# HW2.net
KiCad netlist of a schematic drawn in EAGLE
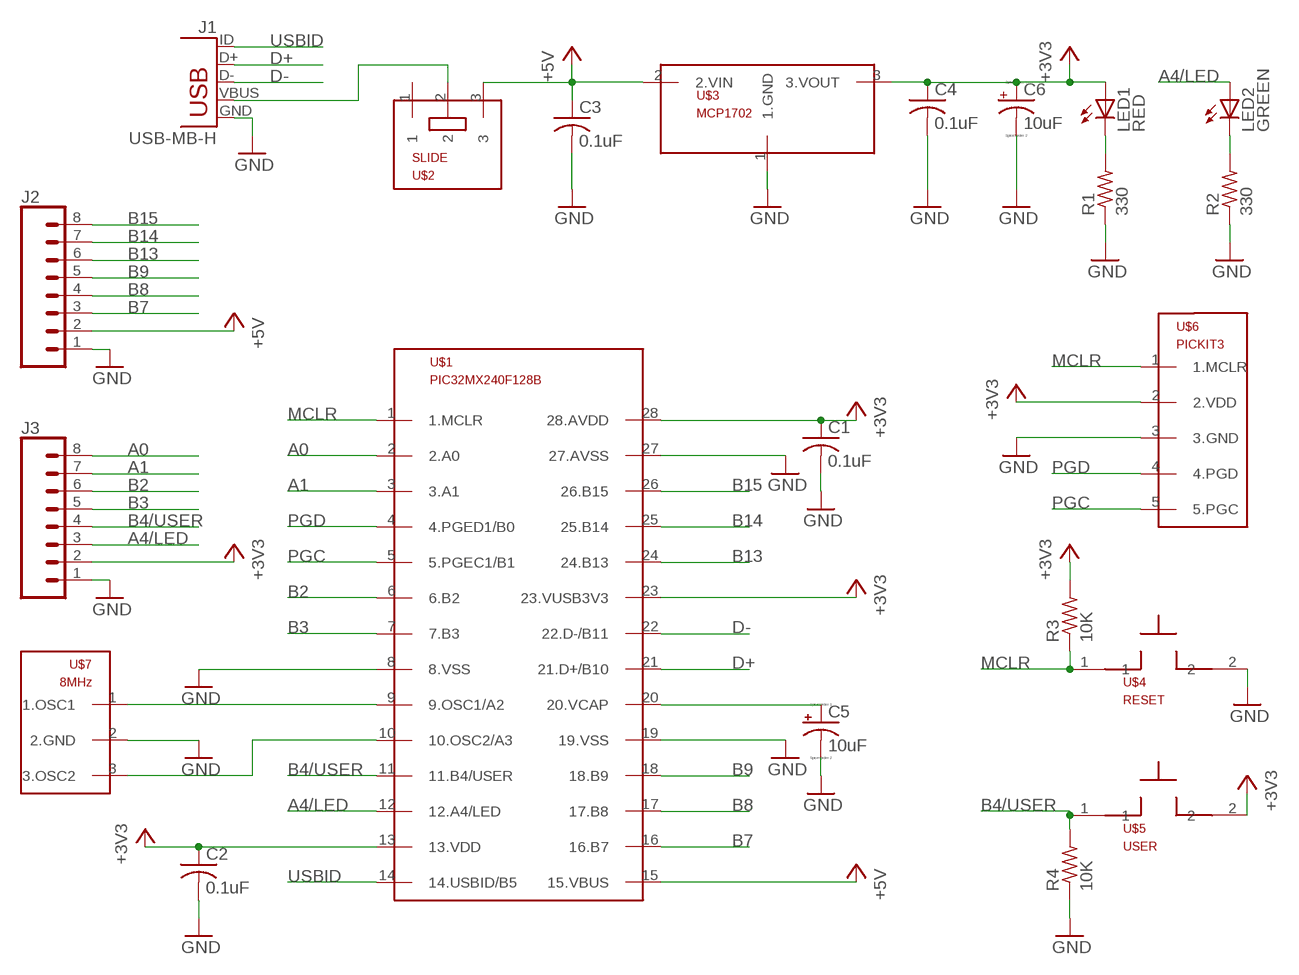
[diagram p0: schematic, sheet 1]

(export (version "E")
  (design (tool "Eeschema 10.0.6"))
  (components
    (comp (ref "C1")
      (value "0.1uF")
      (footprint "eagle-import:C025-025X050")
      (libsource (lib "eagle-import") (part "C-US025-025X050"))
    )
    (comp (ref "C2")
      (value "0.1uF")
      (footprint "eagle-import:C025-025X050")
      (libsource (lib "eagle-import") (part "C-US025-025X050"))
    )
    (comp (ref "C3")
      (value "0.1uF")
      (footprint "eagle-import:C025-025X050")
      (libsource (lib "eagle-import") (part "C-US025-025X050"))
    )
    (comp (ref "C4")
      (value "0.1uF")
      (footprint "eagle-import:C025-025X050")
      (libsource (lib "eagle-import") (part "C-US025-025X050"))
    )
    (comp (ref "C5")
      (value "10uF")
      (footprint "eagle-import:B45181B")
      (libsource (lib "eagle-import") (part "CPOL-USB45181B"))
    )
    (comp (ref "C6")
      (value "10uF")
      (footprint "eagle-import:B45181B")
      (libsource (lib "eagle-import") (part "CPOL-USB45181B"))
    )
    (comp (ref "J1")
      (value "USB-MB-H")
      (footprint "eagle-import:USB-MB-H")
      (libsource (lib "eagle-import") (part "USB-MB-H"))
    )
    (comp (ref "J2")
      (value "CONN_08\"")
      (footprint "eagle-import:1X08")
      (libsource (lib "eagle-import") (part "CONN_08{dblquote}"))
    )
    (comp (ref "J3")
      (value "CONN_08\"")
      (footprint "eagle-import:1X08")
      (libsource (lib "eagle-import") (part "CONN_08{dblquote}"))
    )
    (comp (ref "LED1")
      (value "RED")
      (footprint "eagle-import:LED3MM")
      (libsource (lib "eagle-import") (part "LED3MM"))
    )
    (comp (ref "LED2")
      (value "GREEN")
      (footprint "eagle-import:LED3MM")
      (libsource (lib "eagle-import") (part "LED3MM"))
    )
    (comp (ref "R1")
      (value "330")
      (footprint "eagle-import:0207_10")
      (libsource (lib "eagle-import") (part "R-US_0207/10"))
    )
    (comp (ref "R2")
      (value "330")
      (footprint "eagle-import:0207_10")
      (libsource (lib "eagle-import") (part "R-US_0207/10"))
    )
    (comp (ref "R3")
      (value "10K")
      (footprint "eagle-import:0207_10")
      (libsource (lib "eagle-import") (part "R-US_0207/10"))
    )
    (comp (ref "R4")
      (value "10K")
      (footprint "eagle-import:0207_10")
      (libsource (lib "eagle-import") (part "R-US_0207/10"))
    )
    (comp (ref "U$1")
      (value "PIC32MX240F128B")
      (footprint "eagle-import:DIL28-3")
      (libsource (lib "eagle-import") (part "PIC32MX240F128B"))
    )
    (comp (ref "U$2")
      (value "SLIDE")
      (footprint "eagle-import:SLIDE")
      (libsource (lib "eagle-import") (part "SLIDE"))
    )
    (comp (ref "U$3")
      (value "MCP1702")
      (footprint "eagle-import:TO92")
      (libsource (lib "eagle-import") (part "MCP1702"))
    )
    (comp (ref "U$4")
      (value "RESET")
      (footprint "eagle-import:PUSHBUTTON")
      (libsource (lib "eagle-import") (part "PUSHBUTTON"))
    )
    (comp (ref "U$5")
      (value "USER")
      (footprint "eagle-import:PUSHBUTTON")
      (libsource (lib "eagle-import") (part "PUSHBUTTON"))
    )
    (comp (ref "U$6")
      (value "PICKIT3")
      (footprint "eagle-import:1X05")
      (libsource (lib "eagle-import") (part "PICKIT3"))
    )
    (comp (ref "U$7")
      (value "8MHz")
      (footprint "eagle-import:OSC")
      (libsource (lib "eagle-import") (part "OSC"))
    )
  )
  (nets
    (net (code "1") (name "+3V3") (class "Default")
      (node (ref "C1") (pin "1") (pinfunction "1_1") (pintype "passive"))
      (node (ref "C2") (pin "1") (pinfunction "1_1") (pintype "passive"))
      (node (ref "C4") (pin "1") (pinfunction "1_1") (pintype "passive"))
      (node (ref "C6") (pin "+") (pinfunction "+_+") (pintype "passive"))
      (node (ref "J3") (pin "2") (pinfunction "2_2") (pintype "passive"))
      (node (ref "LED1") (pin "A") (pinfunction "A_A") (pintype "passive"))
      (node (ref "R3") (pin "2") (pinfunction "2_2") (pintype "passive"))
      (node (ref "U$1") (pin "13") (pinfunction "13.VDD_13") (pintype "bidirectional"))
      (node (ref "U$1") (pin "23") (pinfunction "23.VUSB3V3_23") (pintype "bidirectional"))
      (node (ref "U$1") (pin "28") (pinfunction "28.AVDD_28") (pintype "bidirectional"))
      (node (ref "U$3") (pin "3") (pinfunction "3.VOUT_3") (pintype "bidirectional"))
      (node (ref "U$5") (pin "2") (pinfunction "2_2") (pintype "bidirectional"))
      (node (ref "U$6") (pin "2") (pinfunction "2.VDD_2") (pintype "bidirectional"))
    )
    (net (code "2") (name "+5V") (class "Default")
      (node (ref "C3") (pin "1") (pinfunction "1_1") (pintype "passive"))
      (node (ref "J2") (pin "2") (pinfunction "2_2") (pintype "passive"))
      (node (ref "U$1") (pin "15") (pinfunction "15.VBUS_15") (pintype "bidirectional"))
      (node (ref "U$2") (pin "3") (pinfunction "3_3") (pintype "bidirectional"))
      (node (ref "U$3") (pin "2") (pinfunction "2.VIN_2") (pintype "bidirectional"))
    )
    (net (code "3") (name "/A0") (class "Default")
      (node (ref "J3") (pin "8") (pinfunction "8_8") (pintype "passive"))
      (node (ref "U$1") (pin "2") (pinfunction "2.A0_2") (pintype "bidirectional"))
    )
    (net (code "4") (name "/A1") (class "Default")
      (node (ref "J3") (pin "7") (pinfunction "7_7") (pintype "passive"))
      (node (ref "U$1") (pin "3") (pinfunction "3.A1_3") (pintype "bidirectional"))
    )
    (net (code "5") (name "/A4{slash}LED") (class "Default")
      (node (ref "J3") (pin "3") (pinfunction "3_3") (pintype "passive"))
      (node (ref "LED2") (pin "A") (pinfunction "A_A") (pintype "passive"))
      (node (ref "U$1") (pin "12") (pinfunction "12.A4/LED_12") (pintype "bidirectional"))
    )
    (net (code "6") (name "/B2") (class "Default")
      (node (ref "J3") (pin "6") (pinfunction "6_6") (pintype "passive"))
      (node (ref "U$1") (pin "6") (pinfunction "6.B2_6") (pintype "bidirectional"))
    )
    (net (code "7") (name "/B3") (class "Default")
      (node (ref "J3") (pin "5") (pinfunction "5_5") (pintype "passive"))
      (node (ref "U$1") (pin "7") (pinfunction "7.B3_7") (pintype "bidirectional"))
    )
    (net (code "8") (name "/B4{slash}USER") (class "Default")
      (node (ref "J3") (pin "4") (pinfunction "4_4") (pintype "passive"))
      (node (ref "R4") (pin "2") (pinfunction "2_2") (pintype "passive"))
      (node (ref "U$1") (pin "11") (pinfunction "11.B4/USER_11") (pintype "bidirectional"))
      (node (ref "U$5") (pin "1") (pinfunction "1_1") (pintype "bidirectional"))
    )
    (net (code "9") (name "/B7") (class "Default")
      (node (ref "J2") (pin "3") (pinfunction "3_3") (pintype "passive"))
      (node (ref "U$1") (pin "16") (pinfunction "16.B7_16") (pintype "bidirectional"))
    )
    (net (code "10") (name "/B8") (class "Default")
      (node (ref "J2") (pin "4") (pinfunction "4_4") (pintype "passive"))
      (node (ref "U$1") (pin "17") (pinfunction "17.B8_17") (pintype "bidirectional"))
    )
    (net (code "11") (name "/B9") (class "Default")
      (node (ref "J2") (pin "5") (pinfunction "5_5") (pintype "passive"))
      (node (ref "U$1") (pin "18") (pinfunction "18.B9_18") (pintype "bidirectional"))
    )
    (net (code "12") (name "/B13") (class "Default")
      (node (ref "J2") (pin "6") (pinfunction "6_6") (pintype "passive"))
      (node (ref "U$1") (pin "24") (pinfunction "24.B13_24") (pintype "bidirectional"))
    )
    (net (code "13") (name "/B14") (class "Default")
      (node (ref "J2") (pin "7") (pinfunction "7_7") (pintype "passive"))
      (node (ref "U$1") (pin "25") (pinfunction "25.B14_25") (pintype "bidirectional"))
    )
    (net (code "14") (name "/B15") (class "Default")
      (node (ref "J2") (pin "8") (pinfunction "8_8") (pintype "passive"))
      (node (ref "U$1") (pin "26") (pinfunction "26.B15_26") (pintype "bidirectional"))
    )
    (net (code "15") (name "/D+") (class "Default")
      (node (ref "J1") (pin "D+") (pinfunction "D+_D+") (pintype "bidirectional"))
      (node (ref "U$1") (pin "21") (pinfunction "21.D+/B10_21") (pintype "bidirectional"))
    )
    (net (code "16") (name "/D-") (class "Default")
      (node (ref "J1") (pin "D-") (pinfunction "D-_D-") (pintype "bidirectional"))
      (node (ref "U$1") (pin "22") (pinfunction "22.D-/B11_22") (pintype "bidirectional"))
    )
    (net (code "17") (name "/MCLR") (class "Default")
      (node (ref "R3") (pin "1") (pinfunction "1_1") (pintype "passive"))
      (node (ref "U$1") (pin "1") (pinfunction "1.MCLR_1") (pintype "bidirectional"))
      (node (ref "U$4") (pin "1") (pinfunction "1_1") (pintype "bidirectional"))
      (node (ref "U$6") (pin "1") (pinfunction "1.MCLR_1") (pintype "bidirectional"))
    )
    (net (code "18") (name "/PGC") (class "Default")
      (node (ref "U$1") (pin "5") (pinfunction "5.PGEC1/B1_5") (pintype "bidirectional"))
      (node (ref "U$6") (pin "5") (pinfunction "5.PGC_5") (pintype "bidirectional"))
    )
    (net (code "19") (name "/PGD") (class "Default")
      (node (ref "U$1") (pin "4") (pinfunction "4.PGED1/B0_4") (pintype "bidirectional"))
      (node (ref "U$6") (pin "4") (pinfunction "4.PGD_4") (pintype "bidirectional"))
    )
    (net (code "20") (name "/USBID") (class "Default")
      (node (ref "J1") (pin "ID") (pinfunction "ID_ID") (pintype "bidirectional"))
      (node (ref "U$1") (pin "14") (pinfunction "14.USBID/B5_14") (pintype "bidirectional"))
    )
    (net (code "21") (name "GND") (class "Default")
      (node (ref "C1") (pin "2") (pinfunction "2_2") (pintype "passive"))
      (node (ref "C2") (pin "2") (pinfunction "2_2") (pintype "passive"))
      (node (ref "C3") (pin "2") (pinfunction "2_2") (pintype "passive"))
      (node (ref "C4") (pin "2") (pinfunction "2_2") (pintype "passive"))
      (node (ref "C5") (pin "-") (pinfunction "-_-") (pintype "passive"))
      (node (ref "C6") (pin "-") (pinfunction "-_-") (pintype "passive"))
      (node (ref "J1") (pin "GND") (pinfunction "GND_GND") (pintype "bidirectional"))
      (node (ref "J2") (pin "1") (pinfunction "1_1") (pintype "passive"))
      (node (ref "J3") (pin "1") (pinfunction "1_1") (pintype "passive"))
      (node (ref "R1") (pin "1") (pinfunction "1_1") (pintype "passive"))
      (node (ref "R2") (pin "1") (pinfunction "1_1") (pintype "passive"))
      (node (ref "R4") (pin "1") (pinfunction "1_1") (pintype "passive"))
      (node (ref "U$1") (pin "19") (pinfunction "19.VSS_19") (pintype "bidirectional"))
      (node (ref "U$1") (pin "27") (pinfunction "27.AVSS_27") (pintype "bidirectional"))
      (node (ref "U$1") (pin "8") (pinfunction "8.VSS_8") (pintype "bidirectional"))
      (node (ref "U$3") (pin "1") (pinfunction "1.GND_1") (pintype "bidirectional"))
      (node (ref "U$4") (pin "2") (pinfunction "2_2") (pintype "bidirectional"))
      (node (ref "U$6") (pin "3") (pinfunction "3.GND_3") (pintype "bidirectional"))
      (node (ref "U$7") (pin "2") (pinfunction "2.GND_2") (pintype "bidirectional"))
    )
    (net (code "22") (name "Net-(J1-PadVBUS)") (class "Default")
      (node (ref "J1") (pin "VBUS") (pinfunction "VBUS_VBUS") (pintype "bidirectional"))
      (node (ref "U$2") (pin "2") (pinfunction "2_2") (pintype "bidirectional"))
    )
    (net (code "23") (name "Net-(LED1-C)") (class "Default")
      (node (ref "LED1") (pin "K") (pinfunction "C_K") (pintype "passive"))
      (node (ref "R1") (pin "2") (pinfunction "2_2") (pintype "passive"))
    )
    (net (code "24") (name "Net-(LED2-C)") (class "Default")
      (node (ref "LED2") (pin "K") (pinfunction "C_K") (pintype "passive"))
      (node (ref "R2") (pin "2") (pinfunction "2_2") (pintype "passive"))
    )
    (net (code "25") (name "Net-(U$1-9.OSC1{slash}A2)") (class "Default")
      (node (ref "U$1") (pin "9") (pinfunction "9.OSC1/A2_9") (pintype "bidirectional"))
      (node (ref "U$7") (pin "1") (pinfunction "1.OSC1_1") (pintype "bidirectional"))
    )
    (net (code "26") (name "Net-(U$1-10.OSC2{slash}A3)") (class "Default")
      (node (ref "U$1") (pin "10") (pinfunction "10.OSC2/A3_10") (pintype "bidirectional"))
      (node (ref "U$7") (pin "3") (pinfunction "3.OSC2_3") (pintype "bidirectional"))
    )
    (net (code "27") (name "Net-(U$1-20.VCAP)") (class "Default")
      (node (ref "C5") (pin "+") (pinfunction "+_+") (pintype "passive"))
      (node (ref "U$1") (pin "20") (pinfunction "20.VCAP_20") (pintype "bidirectional"))
    )
    (net (code "28") (name "unconnected-(U$2-Pad1)") (class "Default")
      (node (ref "U$2") (pin "1") (pinfunction "1_1") (pintype "bidirectional"))
    )
  )
)
